# rat.net
KiCad netlist of a schematic drawn in EAGLE
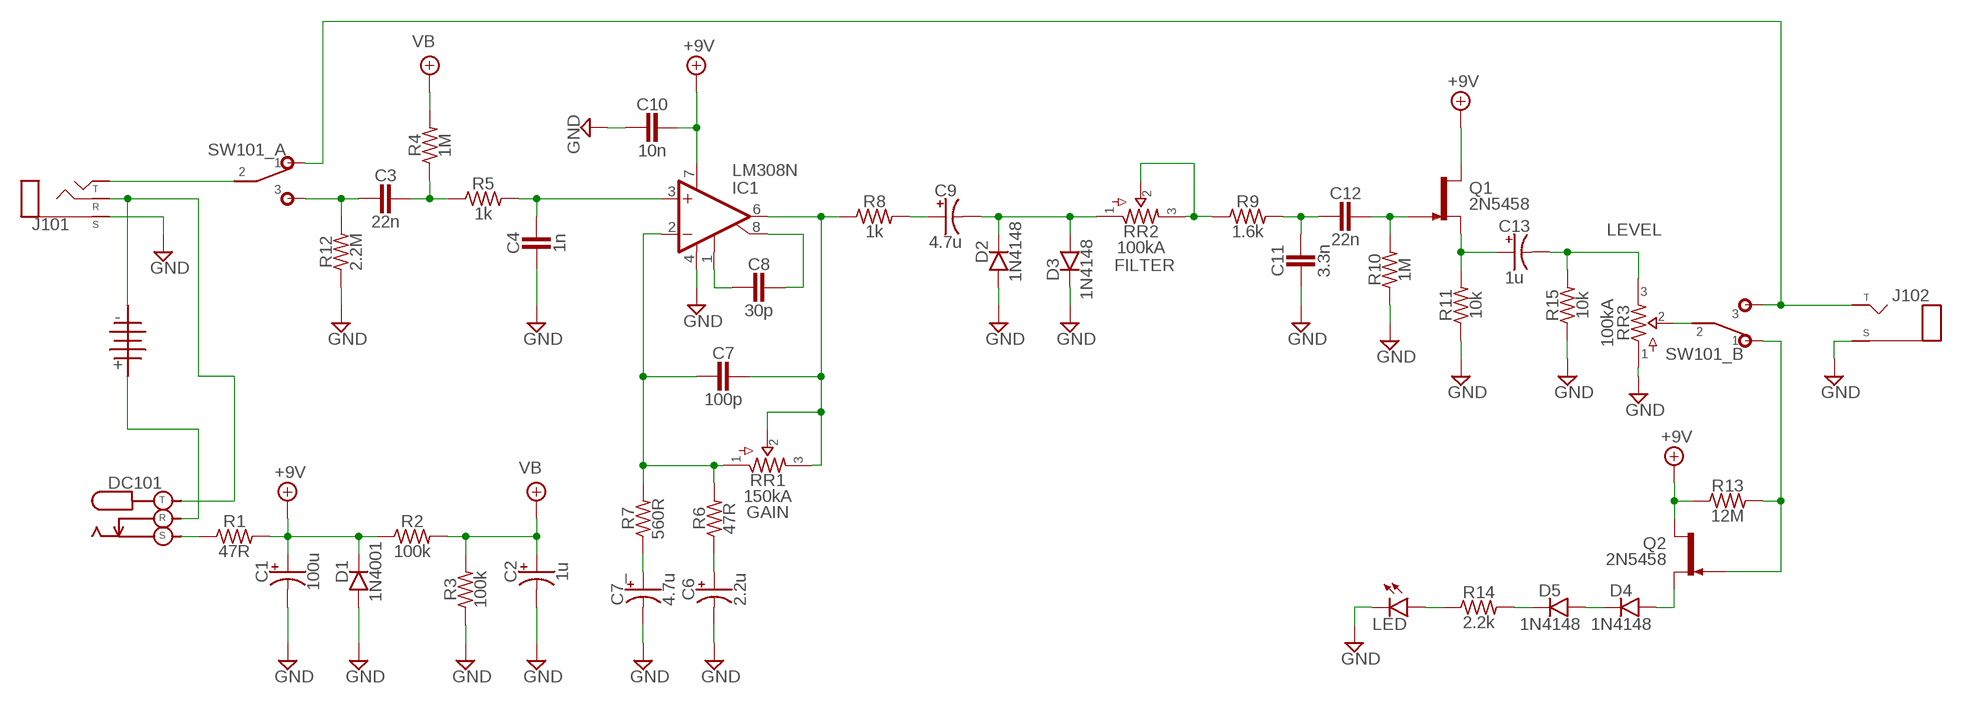
[diagram p0: schematic, sheet 1]

(export (version "E")
  (design (tool "Eeschema 10.0.6"))
  (components
    (comp (ref "1101")
      (value "BATTERY")
      (footprint "eagle-import:TWO_PADS")
      (libsource (lib "eagle-import") (part "BATTERY"))
    )
    (comp (ref "C1")
      (value "100u")
      (footprint "eagle-import:040_020")
      (libsource (lib "eagle-import") (part "0400"))
    )
    (comp (ref "C2")
      (value "1u")
      (footprint "eagle-import:040_020")
      (libsource (lib "eagle-import") (part "0400"))
    )
    (comp (ref "C3")
      (value "22n")
      (footprint "eagle-import:BOX_SMALL")
      (libsource (lib "eagle-import") (part "CER/FILMBOX.1"))
    )
    (comp (ref "C4")
      (value "1n")
      (footprint "eagle-import:BOX_SMALL")
      (libsource (lib "eagle-import") (part "CER/FILMBOX.1"))
    )
    (comp (ref "C6")
      (value "2.2u")
      (footprint "eagle-import:050_020")
      (libsource (lib "eagle-import") (part "0500"))
    )
    (comp (ref "C7")
      (value "100p")
      (footprint "eagle-import:050X030_025_2")
      (libsource (lib "eagle-import") (part "CER/FILM2"))
    )
    (comp (ref "C7_")
      (value "4.7u")
      (footprint "eagle-import:050_020")
      (libsource (lib "eagle-import") (part "0500"))
    )
    (comp (ref "C8")
      (value "30p")
      (footprint "eagle-import:050X030_025_2")
      (libsource (lib "eagle-import") (part "CER/FILM2"))
    )
    (comp (ref "C9")
      (value "4.7u")
      (footprint "eagle-import:050_020")
      (libsource (lib "eagle-import") (part "0500"))
    )
    (comp (ref "C10")
      (value "10n")
      (footprint "eagle-import:050X030_025_2")
      (libsource (lib "eagle-import") (part "CER/FILM2"))
    )
    (comp (ref "C11")
      (value "3.3n")
      (footprint "eagle-import:BOX_SMALL")
      (libsource (lib "eagle-import") (part "CER/FILMBOX.1"))
    )
    (comp (ref "C12")
      (value "22n")
      (footprint "eagle-import:BOX_SMALL")
      (libsource (lib "eagle-import") (part "CER/FILMBOX.1"))
    )
    (comp (ref "C13")
      (value "1u")
      (footprint "eagle-import:050_020")
      (libsource (lib "eagle-import") (part "0500"))
    )
    (comp (ref "D1")
      (value "1N4001")
      (footprint "eagle-import:DO35-2")
      (libsource (lib "eagle-import") (part "DO35.2"))
    )
    (comp (ref "D2")
      (value "1N4148")
      (footprint "eagle-import:DO35-2")
      (libsource (lib "eagle-import") (part "DO35.2"))
    )
    (comp (ref "D3")
      (value "1N4148")
      (footprint "eagle-import:DO35-2")
      (libsource (lib "eagle-import") (part "DO35.2"))
    )
    (comp (ref "D4")
      (value "1N4148")
      (footprint "eagle-import:DO35-2")
      (libsource (lib "eagle-import") (part "DO35.2"))
    )
    (comp (ref "D5")
      (value "1N4148")
      (footprint "eagle-import:DO35-2")
      (libsource (lib "eagle-import") (part "DO35.2"))
    )
    (comp (ref "DC101")
      (value "DC_KOBICONN")
      (footprint "eagle-import:DC_KOBICONN")
      (libsource (lib "eagle-import") (part "DC_KOBICONN"))
    )
    (comp (ref "IC1")
      (value "LM308N")
      (footprint "eagle-import:DIL0")
      (libsource (lib "eagle-import") (part "LM308N"))
    )
    (comp (ref "J101")
      (value "STEREO3PADS")
      (footprint "eagle-import:THREEPADS")
      (libsource (lib "eagle-import") (part "STEREO3PADS"))
    )
    (comp (ref "J102")
      (value "MONO_JACK")
      (footprint "eagle-import:MONO_SW")
      (libsource (lib "eagle-import") (part "MONO_JACK"))
    )
    (comp (ref "LED")
      (value "LED")
      (footprint "eagle-import:3MM_D")
      (libsource (lib "eagle-import") (part "LED"))
    )
    (comp (ref "Q1")
      (value "2N5458")
      (footprint "eagle-import:TO92-")
      (libsource (lib "eagle-import") (part "2N5457"))
    )
    (comp (ref "Q2")
      (value "2N5458")
      (footprint "eagle-import:TO92-")
      (libsource (lib "eagle-import") (part "2N5457"))
    )
    (comp (ref "R1")
      (value "47R")
      (footprint "eagle-import:R0207_3")
      (libsource (lib "eagle-import") (part "R_.3B"))
    )
    (comp (ref "R2")
      (value "100k")
      (footprint "eagle-import:R0207_3")
      (libsource (lib "eagle-import") (part "R_.3B"))
    )
    (comp (ref "R3")
      (value "100k")
      (footprint "eagle-import:R0207_3")
      (libsource (lib "eagle-import") (part "R_.3B"))
    )
    (comp (ref "R4")
      (value "1M")
      (footprint "eagle-import:R0207_3")
      (libsource (lib "eagle-import") (part "R_.3B"))
    )
    (comp (ref "R5")
      (value "1k")
      (footprint "eagle-import:R0207_3")
      (libsource (lib "eagle-import") (part "R_.3B"))
    )
    (comp (ref "R6")
      (value "47R")
      (footprint "eagle-import:R0207_3")
      (libsource (lib "eagle-import") (part "R_.3B"))
    )
    (comp (ref "R7")
      (value "560R")
      (footprint "eagle-import:R0207_3")
      (libsource (lib "eagle-import") (part "R_.3B"))
    )
    (comp (ref "R8")
      (value "1k")
      (footprint "eagle-import:R0207_3")
      (libsource (lib "eagle-import") (part "R_.3B"))
    )
    (comp (ref "R9")
      (value "1.6k")
      (footprint "eagle-import:R0207_3")
      (libsource (lib "eagle-import") (part "R_.3B"))
    )
    (comp (ref "R10")
      (value "1M")
      (footprint "eagle-import:R0207_3")
      (libsource (lib "eagle-import") (part "R_.3B"))
    )
    (comp (ref "R11")
      (value "10k")
      (footprint "eagle-import:R0207_3")
      (libsource (lib "eagle-import") (part "R_.3B"))
    )
    (comp (ref "R12")
      (value "2.2M")
      (footprint "eagle-import:R0207_3")
      (libsource (lib "eagle-import") (part "R_.3B"))
    )
    (comp (ref "R13")
      (value "12M")
      (footprint "eagle-import:R0207_3")
      (libsource (lib "eagle-import") (part "R_.3B"))
    )
    (comp (ref "R14")
      (value "2.2k")
      (footprint "eagle-import:R0207_3")
      (libsource (lib "eagle-import") (part "R_.3B"))
    )
    (comp (ref "R15")
      (value "10k")
      (footprint "eagle-import:R0207_3")
      (libsource (lib "eagle-import") (part "R_.3B"))
    )
    (comp (ref "RR1")
      (value "150kA")
      (footprint "eagle-import:16MM")
      (libsource (lib "eagle-import") (part "POTS16MM"))
    )
    (comp (ref "RR2")
      (value "100kA")
      (footprint "eagle-import:16MM")
      (libsource (lib "eagle-import") (part "POTS16MM"))
    )
    (comp (ref "RR3")
      (value "100kA")
      (footprint "eagle-import:16MM")
      (libsource (lib "eagle-import") (part "POTS16MM"))
    )
    (comp (ref "SW101")
      (value "DPDT")
      (footprint "eagle-import:DPDT")
      (libsource (lib "eagle-import") (part "DPDT"))
    )
  )
  (nets
    (net (code "1") (name "+9V") (class "Default")
      (node (ref "C1") (pin "+") (pinfunction "+_+") (pintype "passive"))
      (node (ref "C10") (pin "1") (pinfunction "1_1") (pintype "passive"))
      (node (ref "D1") (pin "C") (pinfunction "C_C") (pintype "passive"))
      (node (ref "IC1") (pin "7") (pinfunction "V+_7") (pintype "power_in"))
      (node (ref "Q1") (pin "3") (pinfunction "D_3") (pintype "passive"))
      (node (ref "Q2") (pin "3") (pinfunction "D_3") (pintype "passive"))
      (node (ref "R1") (pin "2") (pinfunction "2_2") (pintype "passive"))
      (node (ref "R13") (pin "1") (pinfunction "1_1") (pintype "passive"))
      (node (ref "R2") (pin "1") (pinfunction "1_1") (pintype "passive"))
    )
    (net (code "2") (name "GND") (class "Default")
      (node (ref "C1") (pin "-") (pinfunction "-_-") (pintype "passive"))
      (node (ref "C10") (pin "2") (pinfunction "2_2") (pintype "passive"))
      (node (ref "C11") (pin "2") (pinfunction "2_2") (pintype "passive"))
      (node (ref "C2") (pin "-") (pinfunction "-_-") (pintype "passive"))
      (node (ref "C4") (pin "2") (pinfunction "2_2") (pintype "passive"))
      (node (ref "C6") (pin "-") (pinfunction "-_-") (pintype "passive"))
      (node (ref "C7_") (pin "-") (pinfunction "-_-") (pintype "passive"))
      (node (ref "D1") (pin "A") (pinfunction "A_A") (pintype "passive"))
      (node (ref "D2") (pin "A") (pinfunction "A_A") (pintype "passive"))
      (node (ref "D3") (pin "C") (pinfunction "C_C") (pintype "passive"))
      (node (ref "IC1") (pin "4") (pinfunction "V-_4") (pintype "power_in"))
      (node (ref "J101") (pin "SLEEVE") (pinfunction "S_SLEEVE") (pintype "passive"))
      (node (ref "J102") (pin "S") (pinfunction "SLEEVE_S") (pintype "passive"))
      (node (ref "LED") (pin "P$1") (pinfunction "C_P$1") (pintype "passive"))
      (node (ref "R10") (pin "1") (pinfunction "1_1") (pintype "passive"))
      (node (ref "R11") (pin "1") (pinfunction "1_1") (pintype "passive"))
      (node (ref "R12") (pin "1") (pinfunction "1_1") (pintype "passive"))
      (node (ref "R15") (pin "1") (pinfunction "1_1") (pintype "passive"))
      (node (ref "R3") (pin "1") (pinfunction "1_1") (pintype "passive"))
      (node (ref "RR3") (pin "1") (pinfunction "1_1") (pintype "passive"))
    )
    (net (code "3") (name "Net-(1101-P$1)") (class "Default")
      (node (ref "1101") (pin "T") (pinfunction "P$1_T") (pintype "bidirectional"))
      (node (ref "DC101") (pin "R") (pinfunction "R_R") (pintype "bidirectional"))
    )
    (net (code "4") (name "Net-(1101-P$2)") (class "Default")
      (node (ref "1101") (pin "S") (pinfunction "P$2_S") (pintype "bidirectional"))
      (node (ref "DC101") (pin "T") (pinfunction "T_T") (pintype "bidirectional"))
      (node (ref "J101") (pin "RING") (pinfunction "R_RING") (pintype "passive"))
    )
    (net (code "5") (name "Net-(C3-Pad1)") (class "Default")
      (node (ref "C3") (pin "1") (pinfunction "1_1") (pintype "passive"))
      (node (ref "R4") (pin "1") (pinfunction "1_1") (pintype "passive"))
      (node (ref "R5") (pin "1") (pinfunction "1_1") (pintype "passive"))
    )
    (net (code "6") (name "Net-(C6-Pad+)") (class "Default")
      (node (ref "C6") (pin "+") (pinfunction "+_+") (pintype "passive"))
      (node (ref "R6") (pin "1") (pinfunction "1_1") (pintype "passive"))
    )
    (net (code "7") (name "Net-(C7_-Pad+)") (class "Default")
      (node (ref "C7_") (pin "+") (pinfunction "+_+") (pintype "passive"))
      (node (ref "R7") (pin "1") (pinfunction "1_1") (pintype "passive"))
    )
    (net (code "8") (name "Net-(C9-Pad+)") (class "Default")
      (node (ref "C9") (pin "+") (pinfunction "+_+") (pintype "passive"))
      (node (ref "R8") (pin "2") (pinfunction "2_2") (pintype "passive"))
    )
    (net (code "9") (name "Net-(C9-Pad-)") (class "Default")
      (node (ref "C9") (pin "-") (pinfunction "-_-") (pintype "passive"))
      (node (ref "D2") (pin "C") (pinfunction "C_C") (pintype "passive"))
      (node (ref "D3") (pin "A") (pinfunction "A_A") (pintype "passive"))
      (node (ref "RR2") (pin "1") (pinfunction "1_1") (pintype "passive"))
    )
    (net (code "10") (name "Net-(C11-Pad1)") (class "Default")
      (node (ref "C11") (pin "1") (pinfunction "1_1") (pintype "passive"))
      (node (ref "C12") (pin "2") (pinfunction "2_2") (pintype "passive"))
      (node (ref "R9") (pin "2") (pinfunction "2_2") (pintype "passive"))
    )
    (net (code "11") (name "Net-(C13-Pad-)") (class "Default")
      (node (ref "C13") (pin "-") (pinfunction "-_-") (pintype "passive"))
      (node (ref "R15") (pin "2") (pinfunction "2_2") (pintype "passive"))
      (node (ref "RR3") (pin "3") (pinfunction "3_3") (pintype "passive"))
    )
    (net (code "12") (name "Net-(D4-PadC)") (class "Default")
      (node (ref "D4") (pin "C") (pinfunction "C_C") (pintype "passive"))
      (node (ref "D5") (pin "A") (pinfunction "A_A") (pintype "passive"))
    )
    (net (code "13") (name "Net-(D5-PadC)") (class "Default")
      (node (ref "D5") (pin "C") (pinfunction "C_C") (pintype "passive"))
      (node (ref "R14") (pin "2") (pinfunction "2_2") (pintype "passive"))
    )
    (net (code "14") (name "Net-(DC101-PadS)") (class "Default")
      (node (ref "DC101") (pin "S") (pinfunction "S_S") (pintype "bidirectional"))
      (node (ref "R1") (pin "1") (pinfunction "1_1") (pintype "passive"))
    )
    (net (code "15") (name "Net-(IC1-+IN)") (class "Default")
      (node (ref "C4") (pin "1") (pinfunction "1_1") (pintype "passive"))
      (node (ref "IC1") (pin "3") (pinfunction "+IN_3") (pintype "input"))
      (node (ref "R5") (pin "2") (pinfunction "2_2") (pintype "passive"))
    )
    (net (code "16") (name "Net-(IC1--IN)") (class "Default")
      (node (ref "C7") (pin "2") (pinfunction "2_2") (pintype "passive"))
      (node (ref "IC1") (pin "2") (pinfunction "-IN_2") (pintype "input"))
      (node (ref "R6") (pin "2") (pinfunction "2_2") (pintype "passive"))
      (node (ref "R7") (pin "2") (pinfunction "2_2") (pintype "passive"))
      (node (ref "RR1") (pin "1") (pinfunction "1_1") (pintype "passive"))
    )
    (net (code "17") (name "Net-(IC1-CMP1)") (class "Default")
      (node (ref "C8") (pin "2") (pinfunction "2_2") (pintype "passive"))
      (node (ref "IC1") (pin "1") (pinfunction "CMP1_1") (pintype "passive"))
    )
    (net (code "18") (name "Net-(IC1-CMP2)") (class "Default")
      (node (ref "C8") (pin "1") (pinfunction "1_1") (pintype "passive"))
      (node (ref "IC1") (pin "8") (pinfunction "CMP2_8") (pintype "passive"))
    )
    (net (code "19") (name "Net-(IC1-OUT)") (class "Default")
      (node (ref "C7") (pin "1") (pinfunction "1_1") (pintype "passive"))
      (node (ref "IC1") (pin "6") (pinfunction "OUT_6") (pintype "output"))
      (node (ref "R8") (pin "1") (pinfunction "1_1") (pintype "passive"))
      (node (ref "RR1") (pin "2") (pinfunction "2_2") (pintype "passive"))
      (node (ref "RR1") (pin "3") (pinfunction "3_3") (pintype "passive"))
    )
    (net (code "20") (name "Net-(J101-T)") (class "Default")
      (node (ref "J101") (pin "TIP") (pinfunction "T_TIP") (pintype "passive"))
      (node (ref "SW101") (pin "A2") (pinfunction "2_A2") (pintype "passive"))
    )
    (net (code "21") (name "Net-(J102-TIP)") (class "Default")
      (node (ref "J102") (pin "T") (pinfunction "TIP_T") (pintype "passive"))
      (node (ref "SW101") (pin "A1") (pinfunction "1_A1") (pintype "passive"))
      (node (ref "SW101") (pin "B3") (pinfunction "3_B3") (pintype "passive"))
    )
    (net (code "22") (name "Net-(LED-A)") (class "Default")
      (node (ref "LED") (pin "ANODE") (pinfunction "A_ANODE") (pintype "passive"))
      (node (ref "R14") (pin "1") (pinfunction "1_1") (pintype "passive"))
    )
    (net (code "23") (name "Net-(Q1-G)") (class "Default")
      (node (ref "C12") (pin "1") (pinfunction "1_1") (pintype "passive"))
      (node (ref "Q1") (pin "1") (pinfunction "G_1") (pintype "passive"))
      (node (ref "R10") (pin "2") (pinfunction "2_2") (pintype "passive"))
    )
    (net (code "24") (name "Net-(Q1-S)") (class "Default")
      (node (ref "C13") (pin "+") (pinfunction "+_+") (pintype "passive"))
      (node (ref "Q1") (pin "2") (pinfunction "S_2") (pintype "passive"))
      (node (ref "R11") (pin "2") (pinfunction "2_2") (pintype "passive"))
    )
    (net (code "25") (name "Net-(Q2-G)") (class "Default")
      (node (ref "Q2") (pin "1") (pinfunction "G_1") (pintype "passive"))
      (node (ref "R13") (pin "2") (pinfunction "2_2") (pintype "passive"))
      (node (ref "SW101") (pin "B1") (pinfunction "1_B1") (pintype "passive"))
    )
    (net (code "26") (name "Net-(Q2-S)") (class "Default")
      (node (ref "D4") (pin "A") (pinfunction "A_A") (pintype "passive"))
      (node (ref "Q2") (pin "2") (pinfunction "S_2") (pintype "passive"))
    )
    (net (code "27") (name "Net-(R9-Pad1)") (class "Default")
      (node (ref "R9") (pin "1") (pinfunction "1_1") (pintype "passive"))
      (node (ref "RR2") (pin "2") (pinfunction "2_2") (pintype "passive"))
      (node (ref "RR2") (pin "3") (pinfunction "3_3") (pintype "passive"))
    )
    (net (code "28") (name "Net-(SW101A-3)") (class "Default")
      (node (ref "C3") (pin "2") (pinfunction "2_2") (pintype "passive"))
      (node (ref "R12") (pin "2") (pinfunction "2_2") (pintype "passive"))
      (node (ref "SW101") (pin "A3") (pinfunction "3_A3") (pintype "passive"))
    )
    (net (code "29") (name "Net-(SW101B-2)") (class "Default")
      (node (ref "RR3") (pin "2") (pinfunction "2_2") (pintype "passive"))
      (node (ref "SW101") (pin "B2") (pinfunction "2_B2") (pintype "passive"))
    )
    (net (code "30") (name "VB") (class "Default")
      (node (ref "C2") (pin "+") (pinfunction "+_+") (pintype "passive"))
      (node (ref "R2") (pin "2") (pinfunction "2_2") (pintype "passive"))
      (node (ref "R3") (pin "2") (pinfunction "2_2") (pintype "passive"))
      (node (ref "R4") (pin "2") (pinfunction "2_2") (pintype "passive"))
    )
  )
)
